# Monitoreo-Bateria.net
KiCad netlist of a schematic drawn in Altium Designer
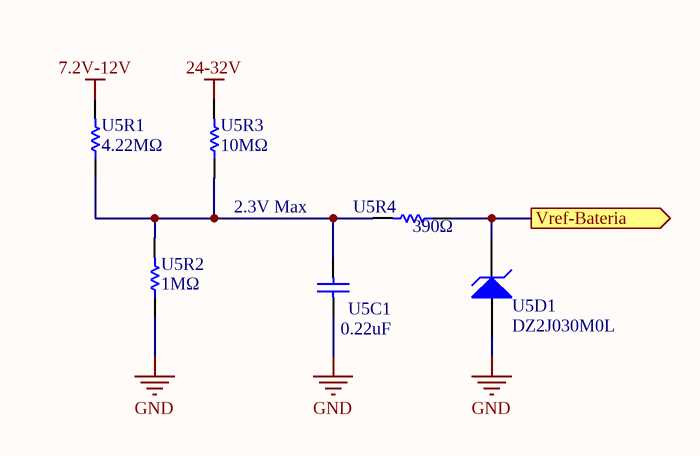
[diagram p0: Monitoreo-Bateria.SchDoc]

(export (version "E")
  (design (tool "Eeschema 10.0.6"))
  (components
    (comp (ref "U5C1")
      (value "0.22uF")
      (footprint "0603 - CAP")
      (description "CAP CER 0.22UF 16V 10% X7R 0603")
      (fields
        (field (name "MANUFACTURER") "Kemet")
        (field (name "MANUFACTURER PART NUMBER") "C0603C224K4RAC7867")
      )
      (libsource (lib "*") (part "Cap"))
    )
    (comp (ref "U5D1")
      (value "DZ2J030M0L")
      (footprint "SOD-323")
      (description "PANASONIC ELECTRONIC COMPONENTS  DZ2J030M0L  DIODE, ZENER, 3.0V, SMINI2-F5-B")
      (fields (field (name "MANUFACTURER") "Panasonic Electronic Components"))
      (libsource (lib "Miscellaneous Devices") (part "D Zener"))
    )
    (comp (ref "U5R1")
      (value "4.22MΩ")
      (footprint "0805-RES")
      (fields
        (field (name "MANUFACTURER") "Vishay Dale")
        (field (name "MANUFACTURER PART NUMBER") "CRCW08054M22FKEA")
      )
      (libsource (lib "Miscellaneous Devices") (part "Res1"))
    )
    (comp (ref "U5R2")
      (value "1MΩ")
      (footprint "0805-RES")
      (fields
        (field (name "MANUFACTURER") "VISHAY")
        (field (name "MANUFACTURER PART NUMBER") "CRCW08051M00FKEA")
      )
      (libsource (lib "Miscellaneous Devices") (part "Res1"))
    )
    (comp (ref "U5R3")
      (value "10MΩ")
      (footprint "0805-RES")
      (fields
        (field (name "MANUFACTURER") "Vishay Dale")
        (field (name "MANUFACTURER PART NUMBER") "CRCW080510M0JNEA")
      )
      (libsource (lib "Miscellaneous Devices") (part "Res1"))
    )
    (comp (ref "U5R4")
      (value "390Ω")
      (footprint "0603-RES")
      (fields
        (field (name "MANUFACTURER") "Yageo")
        (field (name "MANUFACTURER PART NUMBER") "RC0603JR-07390RL")
      )
      (libsource (lib "LibreriaEstandar") (part "Res1"))
    )
  )
  (nets
    (net (code "1") (name "/Vref-Bateria") (class "Default")
      (node (ref "U5D1") (pin "2") (pinfunction "K_2") (pintype "passive"))
      (node (ref "U5R4") (pin "1") (pinfunction "1_1") (pintype "passive"))
    )
    (net (code "2") (name "7.2V-12V") (class "Default")
      (node (ref "U5R1") (pin "2") (pinfunction "2_2") (pintype "passive"))
    )
    (net (code "3") (name "24-32V") (class "Default")
      (node (ref "U5R3") (pin "2") (pinfunction "2_2") (pintype "passive"))
    )
    (net (code "4") (name "GND") (class "Default")
      (node (ref "U5C1") (pin "2") (pinfunction "2_2") (pintype "passive"))
      (node (ref "U5D1") (pin "1") (pinfunction "A_1") (pintype "passive"))
      (node (ref "U5R2") (pin "1") (pinfunction "1_1") (pintype "passive"))
    )
    (net (code "5") (name "Net-(U5C1-Pad1)") (class "Default")
      (node (ref "U5C1") (pin "1") (pinfunction "1_1") (pintype "passive"))
      (node (ref "U5R1") (pin "1") (pinfunction "1_1") (pintype "passive"))
      (node (ref "U5R2") (pin "2") (pinfunction "2_2") (pintype "passive"))
      (node (ref "U5R3") (pin "1") (pinfunction "1_1") (pintype "passive"))
      (node (ref "U5R4") (pin "2") (pinfunction "2_2") (pintype "passive"))
    )
  )
)
